# RB01.net
KiCad netlist of a schematic drawn in EAGLE
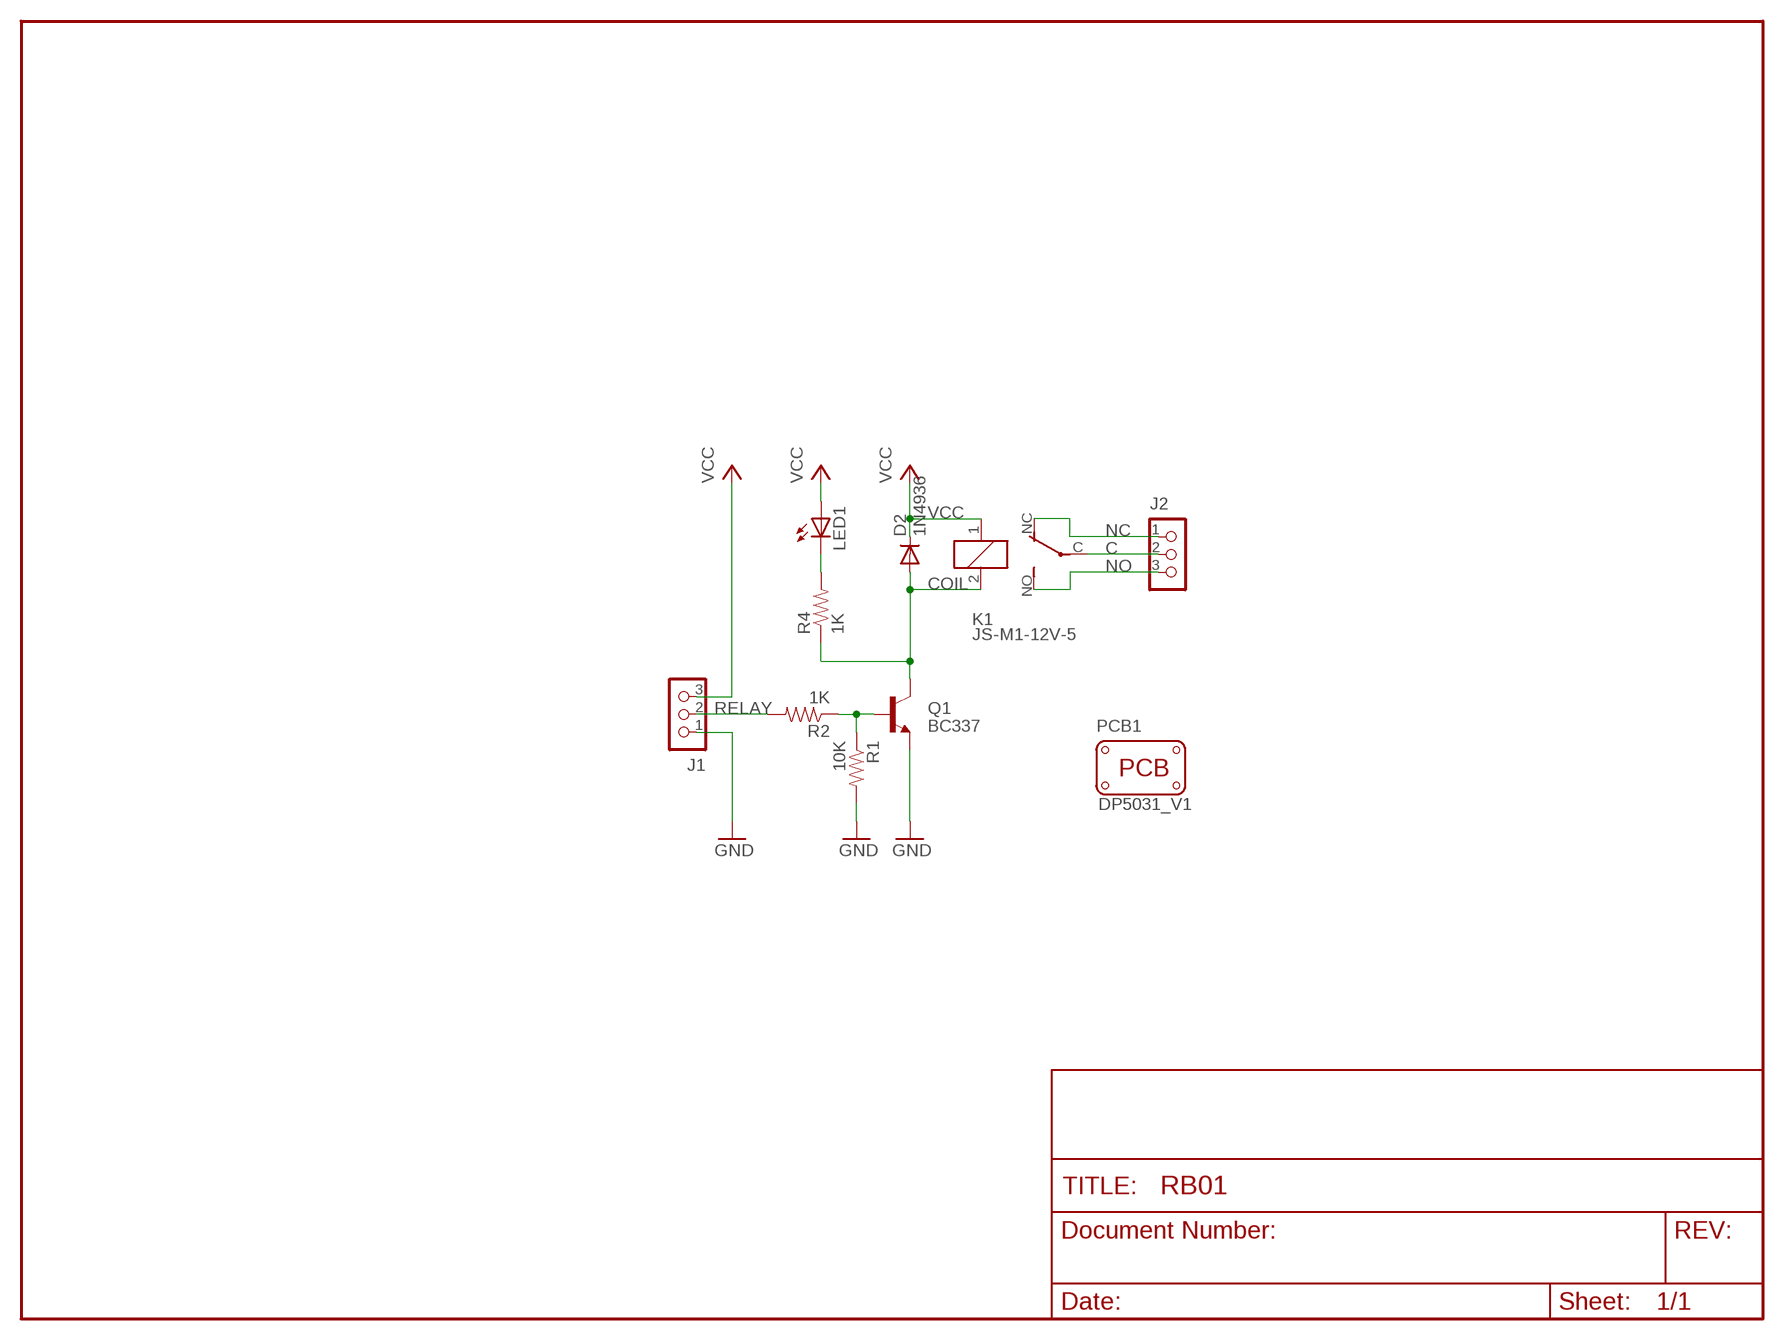
[diagram p0: schematic, sheet 1]

(export (version "E")
  (design (tool "Eeschema 10.0.6"))
  (components
    (comp (ref "D2")
      (value "1N4936")
      (footprint "eagle-import:DO41-10")
      (libsource (lib "eagle-import") (part "1N4933"))
    )
    (comp (ref "J1")
      (value "CON_TERMINAL_BLOCK_03-5MM")
      (footprint "eagle-import:TERMINAL_BLOCK_3P_5")
      (libsource (lib "eagle-import") (part "CON_TERMINAL_BLOCK_03-5MM"))
    )
    (comp (ref "J2")
      (value "CON_TERMINAL_BLOCK_03-5MM")
      (footprint "eagle-import:TERMINAL_BLOCK_3P_5")
      (libsource (lib "eagle-import") (part "CON_TERMINAL_BLOCK_03-5MM"))
    )
    (comp (ref "K1")
      (value "JS-M1-12V-5")
      (footprint "eagle-import:JS-M")
      (fields
        (field (name "MF") "FARNELL")
        (field (name "MPN") "JSM1-12V-5")
        (field (name "MF_1") "FARNELL")
        (field (name "MPN_1") "JSM1-12V-5")
        (field (name "OC_FARNELL") "910351")
        (field (name "OC_NEWARK") "14J1764")
      )
      (libsource (lib "eagle-import") (part "JS-M1-12V-5"))
    )
    (comp (ref "LED1")
      (value "LED-3MM")
      (footprint "eagle-import:LED-3MM")
      (libsource (lib "eagle-import") (part "LED-3MM"))
    )
    (comp (ref "PCB1")
      (value "PCB_DP_RECTANGLE-31X50")
      (footprint "eagle-import:DP5031_V1")
      (libsource (lib "eagle-import") (part "PCB_DP_RECTANGLE-31X50"))
    )
    (comp (ref "Q1")
      (value "BC337")
      (footprint "eagle-import:TO92")
      (libsource (lib "eagle-import") (part "BC337"))
    )
    (comp (ref "R1")
      (value "10K")
      (footprint "eagle-import:AXIAL-0.3")
      (libsource (lib "eagle-import") (part "RESISTORAXIAL-0.3"))
    )
    (comp (ref "R2")
      (value "1K")
      (footprint "eagle-import:AXIAL-0.3")
      (libsource (lib "eagle-import") (part "RESISTORAXIAL-0.3"))
    )
    (comp (ref "R4")
      (value "1K")
      (footprint "eagle-import:AXIAL-0.3")
      (libsource (lib "eagle-import") (part "RESISTORAXIAL-0.3"))
    )
  )
  (nets
    (net (code "1") (name "/C") (class "Default")
      (node (ref "J2") (pin "2") (pinfunction "2_2") (pintype "bidirectional"))
      (node (ref "K1") (pin "C") (pinfunction "P_C") (pintype "passive"))
    )
    (net (code "2") (name "/COIL") (class "Default")
      (node (ref "D2") (pin "A") (pinfunction "A_A") (pintype "passive"))
      (node (ref "K1") (pin "2") (pinfunction "2_2") (pintype "passive"))
      (node (ref "Q1") (pin "3") (pinfunction "C_3") (pintype "passive"))
      (node (ref "R4") (pin "P$1") (pinfunction "1_P$1") (pintype "passive"))
    )
    (net (code "3") (name "/NC") (class "Default")
      (node (ref "J2") (pin "1") (pinfunction "1_1") (pintype "bidirectional"))
      (node (ref "K1") (pin "NC") (pinfunction "O_NC") (pintype "passive"))
    )
    (net (code "4") (name "/NO") (class "Default")
      (node (ref "J2") (pin "3") (pinfunction "3_3") (pintype "bidirectional"))
      (node (ref "K1") (pin "NO") (pinfunction "S_NO") (pintype "passive"))
    )
    (net (code "5") (name "/RELAY") (class "Default")
      (node (ref "J1") (pin "2") (pinfunction "2_2") (pintype "bidirectional"))
      (node (ref "R2") (pin "P$2") (pinfunction "2_P$2") (pintype "passive"))
    )
    (net (code "6") (name "GND") (class "Default")
      (node (ref "J1") (pin "1") (pinfunction "1_1") (pintype "bidirectional"))
      (node (ref "Q1") (pin "1") (pinfunction "E_1") (pintype "passive"))
      (node (ref "R1") (pin "P$2") (pinfunction "2_P$2") (pintype "passive"))
    )
    (net (code "7") (name "Net-(LED1-C)") (class "Default")
      (node (ref "LED1") (pin "K") (pinfunction "C_K") (pintype "passive"))
      (node (ref "R4") (pin "P$2") (pinfunction "2_P$2") (pintype "passive"))
    )
    (net (code "8") (name "Net-(Q1-B)") (class "Default")
      (node (ref "Q1") (pin "2") (pinfunction "B_2") (pintype "passive"))
      (node (ref "R1") (pin "P$1") (pinfunction "1_P$1") (pintype "passive"))
      (node (ref "R2") (pin "P$1") (pinfunction "1_P$1") (pintype "passive"))
    )
    (net (code "9") (name "VCC") (class "Default")
      (node (ref "D2") (pin "C") (pinfunction "C_C") (pintype "passive"))
      (node (ref "J1") (pin "3") (pinfunction "3_3") (pintype "bidirectional"))
      (node (ref "K1") (pin "1") (pinfunction "1_1") (pintype "passive"))
      (node (ref "LED1") (pin "A") (pinfunction "A_A") (pintype "passive"))
    )
  )
)
